# Capteurs.net
KiCad netlist of a schematic drawn in EAGLE
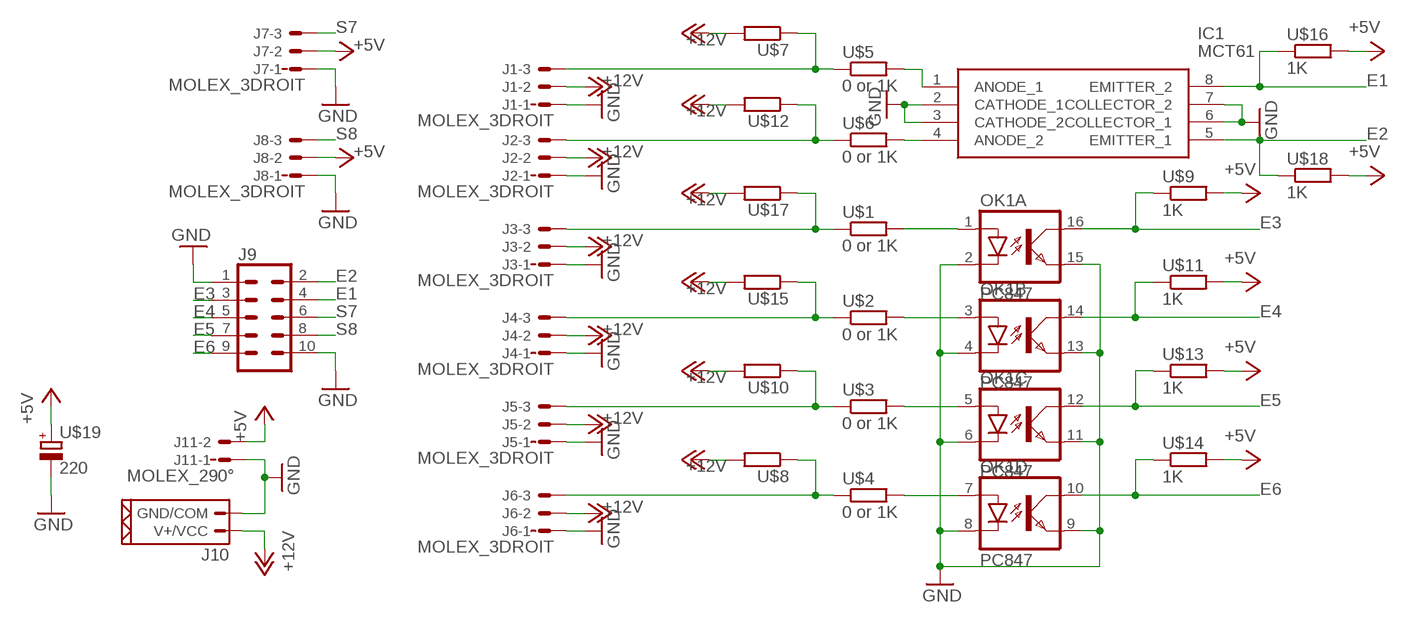
[diagram p0: schematic, sheet 1]

(export (version "E")
  (design (tool "Eeschema 10.0.6"))
  (components
    (comp (ref "IC1")
      (value "MCT61")
      (footprint "eagle-import:DIP762W56P254L940H508Q8N")
      (fields (field (name "MOUSER_PART_NUMBER") "512-MCT61") (field (name "RS_PART_NUMBER") "7613552P"))
      (libsource (lib "eagle-import") (part "MCT61"))
    )
    (comp (ref "J1")
      (value "MOLEX_3DROIT")
      (footprint "eagle-import:CON_3_DROIT")
      (fields (field (name "MF") "MOLEX"))
      (libsource (lib "eagle-import") (part "MOLEX_3DROIT"))
    )
    (comp (ref "J2")
      (value "MOLEX_3DROIT")
      (footprint "eagle-import:CON_3_DROIT")
      (fields (field (name "MF") "MOLEX"))
      (libsource (lib "eagle-import") (part "MOLEX_3DROIT"))
    )
    (comp (ref "J3")
      (value "MOLEX_3DROIT")
      (footprint "eagle-import:CON_3_DROIT")
      (fields (field (name "MF") "MOLEX"))
      (libsource (lib "eagle-import") (part "MOLEX_3DROIT"))
    )
    (comp (ref "J4")
      (value "MOLEX_3DROIT")
      (footprint "eagle-import:CON_3_DROIT")
      (fields (field (name "MF") "MOLEX"))
      (libsource (lib "eagle-import") (part "MOLEX_3DROIT"))
    )
    (comp (ref "J5")
      (value "MOLEX_3DROIT")
      (footprint "eagle-import:CON_3_DROIT")
      (fields (field (name "MF") "MOLEX"))
      (libsource (lib "eagle-import") (part "MOLEX_3DROIT"))
    )
    (comp (ref "J6")
      (value "MOLEX_3DROIT")
      (footprint "eagle-import:CON_3_DROIT")
      (fields (field (name "MF") "MOLEX"))
      (libsource (lib "eagle-import") (part "MOLEX_3DROIT"))
    )
    (comp (ref "J7")
      (value "MOLEX_3DROIT")
      (footprint "eagle-import:CON_3_DROIT")
      (fields (field (name "MF") "MOLEX"))
      (libsource (lib "eagle-import") (part "MOLEX_3DROIT"))
    )
    (comp (ref "J8")
      (value "MOLEX_3DROIT")
      (footprint "eagle-import:CON_3_DROIT")
      (fields (field (name "MF") "MOLEX"))
      (libsource (lib "eagle-import") (part "MOLEX_3DROIT"))
    )
    (comp (ref "J9")
      (value "CON_5X2SHD")
      (footprint "eagle-import:2X5-SHROUDED")
      (libsource (lib "eagle-import") (part "CON_5X2SHD"))
    )
    (comp (ref "J10")
      (value "MOLEX_2_PUISS90°")
      (footprint "eagle-import:CON_2_PUISS_90°")
      (libsource (lib "eagle-import") (part "MOLEX_2_PUISS90°"))
    )
    (comp (ref "J11")
      (value "MOLEX_290°")
      (footprint "eagle-import:CON_2_90°")
      (fields (field (name "MF") "MOLEX"))
      (libsource (lib "eagle-import") (part "MOLEX_290°"))
    )
    (comp (ref "OK1")
      (value "PC847")
      (footprint "eagle-import:DIL16")
      (libsource (lib "eagle-import") (part "PC847"))
    )
    (comp (ref "U$1")
      (value "0 or 1K")
      (footprint "eagle-import:R1206")
      (libsource (lib "eagle-import") (part "R1206R1206"))
    )
    (comp (ref "U$2")
      (value "0 or 1K")
      (footprint "eagle-import:R1206")
      (libsource (lib "eagle-import") (part "R1206R1206"))
    )
    (comp (ref "U$3")
      (value "0 or 1K")
      (footprint "eagle-import:R1206")
      (libsource (lib "eagle-import") (part "R1206R1206"))
    )
    (comp (ref "U$4")
      (value "0 or 1K")
      (footprint "eagle-import:R1206")
      (libsource (lib "eagle-import") (part "R1206R1206"))
    )
    (comp (ref "U$5")
      (value "0 or 1K")
      (footprint "eagle-import:R1206")
      (libsource (lib "eagle-import") (part "R1206R1206"))
    )
    (comp (ref "U$6")
      (value "0 or 1K")
      (footprint "eagle-import:R1206")
      (libsource (lib "eagle-import") (part "R1206R1206"))
    )
    (comp (ref "U$7")
      (value "NULL or 500")
      (footprint "eagle-import:R1206")
      (libsource (lib "eagle-import") (part "R1206R1206"))
    )
    (comp (ref "U$8")
      (value "NULL or 500")
      (footprint "eagle-import:R1206")
      (libsource (lib "eagle-import") (part "R1206R1206"))
    )
    (comp (ref "U$9")
      (value "1K")
      (footprint "eagle-import:R1206")
      (libsource (lib "eagle-import") (part "R1206R1206"))
    )
    (comp (ref "U$10")
      (value "NULL or 500")
      (footprint "eagle-import:R1206")
      (libsource (lib "eagle-import") (part "R1206R1206"))
    )
    (comp (ref "U$11")
      (value "1K")
      (footprint "eagle-import:R1206")
      (libsource (lib "eagle-import") (part "R1206R1206"))
    )
    (comp (ref "U$12")
      (value "NULL or 500")
      (footprint "eagle-import:R1206")
      (libsource (lib "eagle-import") (part "R1206R1206"))
    )
    (comp (ref "U$13")
      (value "1K")
      (footprint "eagle-import:R1206")
      (libsource (lib "eagle-import") (part "R1206R1206"))
    )
    (comp (ref "U$14")
      (value "1K")
      (footprint "eagle-import:R1206")
      (libsource (lib "eagle-import") (part "R1206R1206"))
    )
    (comp (ref "U$15")
      (value "NULL or 500")
      (footprint "eagle-import:R1206")
      (libsource (lib "eagle-import") (part "R1206R1206"))
    )
    (comp (ref "U$16")
      (value "1K")
      (footprint "eagle-import:R1206")
      (libsource (lib "eagle-import") (part "R1206R1206"))
    )
    (comp (ref "U$17")
      (value "NULL or 500")
      (footprint "eagle-import:R1206")
      (libsource (lib "eagle-import") (part "R1206R1206"))
    )
    (comp (ref "U$18")
      (value "1K")
      (footprint "eagle-import:R1206")
      (libsource (lib "eagle-import") (part "R1206R1206"))
    )
    (comp (ref "U$19")
      (value "220")
      (footprint "eagle-import:E3,5-8")
      (libsource (lib "eagle-import") (part "CONDO3.5-8"))
    )
  )
  (nets
    (net (code "1") (name "+5V") (class "Default")
      (node (ref "J11") (pin "2") (pinfunction "S_2") (pintype "passive"))
      (node (ref "J7") (pin "2") (pinfunction "S_2") (pintype "passive"))
      (node (ref "J8") (pin "2") (pinfunction "S_2") (pintype "passive"))
      (node (ref "U$11") (pin "2") (pinfunction "2_2") (pintype "passive"))
      (node (ref "U$13") (pin "2") (pinfunction "2_2") (pintype "passive"))
      (node (ref "U$14") (pin "2") (pinfunction "2_2") (pintype "passive"))
      (node (ref "U$16") (pin "2") (pinfunction "2_2") (pintype "passive"))
      (node (ref "U$18") (pin "2") (pinfunction "2_2") (pintype "passive"))
      (node (ref "U$19") (pin "+") (pinfunction "+_+") (pintype "passive"))
      (node (ref "U$9") (pin "2") (pinfunction "2_2") (pintype "passive"))
    )
    (net (code "2") (name "+12V") (class "Default")
      (node (ref "J1") (pin "2") (pinfunction "S_2") (pintype "passive"))
      (node (ref "J10") (pin "P$2") (pinfunction "V+/VCC_P$2") (pintype "passive"))
      (node (ref "J2") (pin "2") (pinfunction "S_2") (pintype "passive"))
      (node (ref "J3") (pin "2") (pinfunction "S_2") (pintype "passive"))
      (node (ref "J4") (pin "2") (pinfunction "S_2") (pintype "passive"))
      (node (ref "J5") (pin "2") (pinfunction "S_2") (pintype "passive"))
      (node (ref "J6") (pin "2") (pinfunction "S_2") (pintype "passive"))
      (node (ref "U$10") (pin "2") (pinfunction "2_2") (pintype "passive"))
      (node (ref "U$12") (pin "2") (pinfunction "2_2") (pintype "passive"))
      (node (ref "U$15") (pin "2") (pinfunction "2_2") (pintype "passive"))
      (node (ref "U$17") (pin "2") (pinfunction "2_2") (pintype "passive"))
      (node (ref "U$7") (pin "2") (pinfunction "2_2") (pintype "passive"))
      (node (ref "U$8") (pin "2") (pinfunction "2_2") (pintype "passive"))
    )
    (net (code "3") (name "/E1") (class "Default")
      (node (ref "IC1") (pin "8") (pinfunction "EMITTER_2_8") (pintype "bidirectional"))
      (node (ref "J9") (pin "4") (pinfunction "4_4") (pintype "passive"))
      (node (ref "U$16") (pin "1") (pinfunction "1_1") (pintype "passive"))
    )
    (net (code "4") (name "/E2") (class "Default")
      (node (ref "IC1") (pin "5") (pinfunction "EMITTER_1_5") (pintype "bidirectional"))
      (node (ref "J9") (pin "2") (pinfunction "2_2") (pintype "passive"))
      (node (ref "U$18") (pin "1") (pinfunction "1_1") (pintype "passive"))
    )
    (net (code "5") (name "/E3") (class "Default")
      (node (ref "J9") (pin "3") (pinfunction "3_3") (pintype "passive"))
      (node (ref "OK1") (pin "16") (pinfunction "COL_16") (pintype "passive"))
      (node (ref "U$9") (pin "1") (pinfunction "1_1") (pintype "passive"))
    )
    (net (code "6") (name "/E4") (class "Default")
      (node (ref "J9") (pin "5") (pinfunction "5_5") (pintype "passive"))
      (node (ref "OK1") (pin "14") (pinfunction "COL_14") (pintype "passive"))
      (node (ref "U$11") (pin "1") (pinfunction "1_1") (pintype "passive"))
    )
    (net (code "7") (name "/E5") (class "Default")
      (node (ref "J9") (pin "7") (pinfunction "7_7") (pintype "passive"))
      (node (ref "OK1") (pin "12") (pinfunction "COL_12") (pintype "passive"))
      (node (ref "U$13") (pin "1") (pinfunction "1_1") (pintype "passive"))
    )
    (net (code "8") (name "/E6") (class "Default")
      (node (ref "J9") (pin "9") (pinfunction "9_9") (pintype "passive"))
      (node (ref "OK1") (pin "10") (pinfunction "COL_10") (pintype "passive"))
      (node (ref "U$14") (pin "1") (pinfunction "1_1") (pintype "passive"))
    )
    (net (code "9") (name "/S7") (class "Default")
      (node (ref "J7") (pin "3") (pinfunction "S_3") (pintype "passive"))
      (node (ref "J9") (pin "6") (pinfunction "6_6") (pintype "passive"))
    )
    (net (code "10") (name "/S8") (class "Default")
      (node (ref "J8") (pin "3") (pinfunction "S_3") (pintype "passive"))
      (node (ref "J9") (pin "8") (pinfunction "8_8") (pintype "passive"))
    )
    (net (code "11") (name "GND") (class "Default")
      (node (ref "IC1") (pin "2") (pinfunction "CATHODE_1_2") (pintype "bidirectional"))
      (node (ref "IC1") (pin "3") (pinfunction "CATHODE_2_3") (pintype "bidirectional"))
      (node (ref "IC1") (pin "6") (pinfunction "COLLECTOR_1_6") (pintype "bidirectional"))
      (node (ref "IC1") (pin "7") (pinfunction "COLLECTOR_2_7") (pintype "bidirectional"))
      (node (ref "J1") (pin "1") (pinfunction "S_1") (pintype "passive"))
      (node (ref "J10") (pin "P$1") (pinfunction "GND/COM_P$1") (pintype "passive"))
      (node (ref "J11") (pin "1") (pinfunction "S_1") (pintype "passive"))
      (node (ref "J2") (pin "1") (pinfunction "S_1") (pintype "passive"))
      (node (ref "J3") (pin "1") (pinfunction "S_1") (pintype "passive"))
      (node (ref "J4") (pin "1") (pinfunction "S_1") (pintype "passive"))
      (node (ref "J5") (pin "1") (pinfunction "S_1") (pintype "passive"))
      (node (ref "J6") (pin "1") (pinfunction "S_1") (pintype "passive"))
      (node (ref "J7") (pin "1") (pinfunction "S_1") (pintype "passive"))
      (node (ref "J8") (pin "1") (pinfunction "S_1") (pintype "passive"))
      (node (ref "J9") (pin "1") (pinfunction "1_1") (pintype "passive"))
      (node (ref "J9") (pin "10") (pinfunction "10_10") (pintype "passive"))
      (node (ref "OK1") (pin "11") (pinfunction "EMIT_11") (pintype "passive"))
      (node (ref "OK1") (pin "13") (pinfunction "EMIT_13") (pintype "passive"))
      (node (ref "OK1") (pin "15") (pinfunction "EMIT_15") (pintype "passive"))
      (node (ref "OK1") (pin "2") (pinfunction "C_2") (pintype "passive"))
      (node (ref "OK1") (pin "4") (pinfunction "C_4") (pintype "passive"))
      (node (ref "OK1") (pin "6") (pinfunction "C_6") (pintype "passive"))
      (node (ref "OK1") (pin "8") (pinfunction "C_8") (pintype "passive"))
      (node (ref "OK1") (pin "9") (pinfunction "EMIT_9") (pintype "passive"))
      (node (ref "U$19") (pin "-") (pinfunction "-_-") (pintype "passive"))
    )
    (net (code "12") (name "Net-(IC1-ANODE_1)") (class "Default")
      (node (ref "IC1") (pin "1") (pinfunction "ANODE_1_1") (pintype "bidirectional"))
      (node (ref "U$5") (pin "2") (pinfunction "2_2") (pintype "passive"))
    )
    (net (code "13") (name "Net-(IC1-ANODE_2)") (class "Default")
      (node (ref "IC1") (pin "4") (pinfunction "ANODE_2_4") (pintype "bidirectional"))
      (node (ref "U$6") (pin "2") (pinfunction "2_2") (pintype "passive"))
    )
    (net (code "14") (name "Net-(J1C-S)") (class "Default")
      (node (ref "J1") (pin "3") (pinfunction "S_3") (pintype "passive"))
      (node (ref "U$5") (pin "1") (pinfunction "1_1") (pintype "passive"))
      (node (ref "U$7") (pin "1") (pinfunction "1_1") (pintype "passive"))
    )
    (net (code "15") (name "Net-(J2C-S)") (class "Default")
      (node (ref "J2") (pin "3") (pinfunction "S_3") (pintype "passive"))
      (node (ref "U$12") (pin "1") (pinfunction "1_1") (pintype "passive"))
      (node (ref "U$6") (pin "1") (pinfunction "1_1") (pintype "passive"))
    )
    (net (code "16") (name "Net-(J3C-S)") (class "Default")
      (node (ref "J3") (pin "3") (pinfunction "S_3") (pintype "passive"))
      (node (ref "U$1") (pin "1") (pinfunction "1_1") (pintype "passive"))
      (node (ref "U$17") (pin "1") (pinfunction "1_1") (pintype "passive"))
    )
    (net (code "17") (name "Net-(J4C-S)") (class "Default")
      (node (ref "J4") (pin "3") (pinfunction "S_3") (pintype "passive"))
      (node (ref "U$15") (pin "1") (pinfunction "1_1") (pintype "passive"))
      (node (ref "U$2") (pin "1") (pinfunction "1_1") (pintype "passive"))
    )
    (net (code "18") (name "Net-(J5C-S)") (class "Default")
      (node (ref "J5") (pin "3") (pinfunction "S_3") (pintype "passive"))
      (node (ref "U$10") (pin "1") (pinfunction "1_1") (pintype "passive"))
      (node (ref "U$3") (pin "1") (pinfunction "1_1") (pintype "passive"))
    )
    (net (code "19") (name "Net-(J6C-S)") (class "Default")
      (node (ref "J6") (pin "3") (pinfunction "S_3") (pintype "passive"))
      (node (ref "U$4") (pin "1") (pinfunction "1_1") (pintype "passive"))
      (node (ref "U$8") (pin "1") (pinfunction "1_1") (pintype "passive"))
    )
    (net (code "20") (name "Net-(OK1A-A)") (class "Default")
      (node (ref "OK1") (pin "1") (pinfunction "A_1") (pintype "passive"))
      (node (ref "U$1") (pin "2") (pinfunction "2_2") (pintype "passive"))
    )
    (net (code "21") (name "Net-(OK1B-A)") (class "Default")
      (node (ref "OK1") (pin "3") (pinfunction "A_3") (pintype "passive"))
      (node (ref "U$2") (pin "2") (pinfunction "2_2") (pintype "passive"))
    )
    (net (code "22") (name "Net-(OK1C-A)") (class "Default")
      (node (ref "OK1") (pin "5") (pinfunction "A_5") (pintype "passive"))
      (node (ref "U$3") (pin "2") (pinfunction "2_2") (pintype "passive"))
    )
    (net (code "23") (name "Net-(OK1D-A)") (class "Default")
      (node (ref "OK1") (pin "7") (pinfunction "A_7") (pintype "passive"))
      (node (ref "U$4") (pin "2") (pinfunction "2_2") (pintype "passive"))
    )
  )
)
